# EtherWiz_A4.net
KiCad netlist of a schematic drawn in Altium Designer
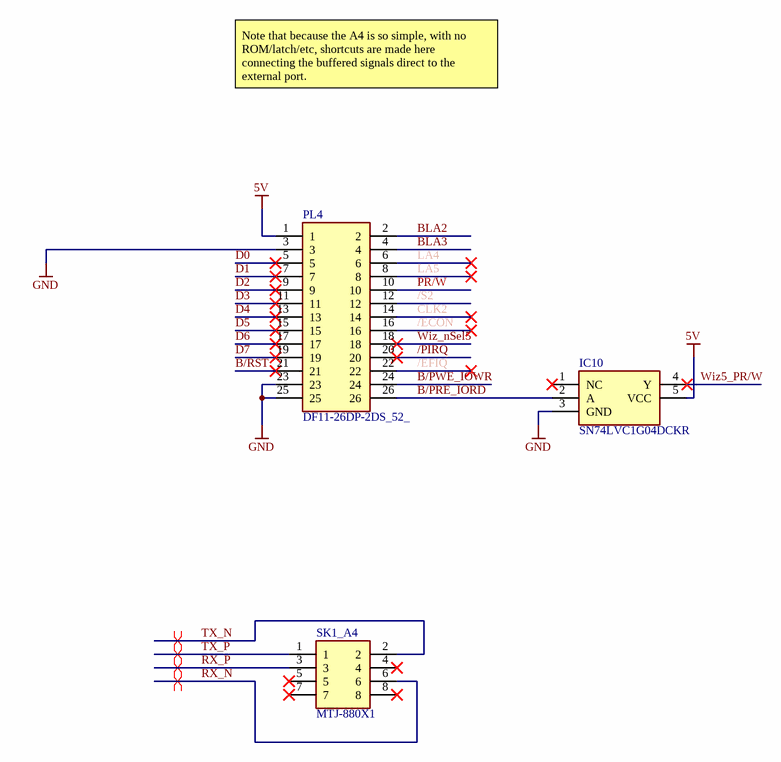
[diagram p0: EtherWiz_A4.SchDoc]

(export (version "E")
  (design (tool "Eeschema 10.0.6"))
  (components
    (comp (ref "IC10")
      (value "SN74LVC1G04DCKR")
      (footprint "SamacSys:SOT65P210X110-5N")
      (description "Integrated Circuit")
      (fields (field (name "MOUSER PART NUMBER") "595-SN74LVC1G04DCKR"))
      (libsource (lib "*") (part "SN74LVC1G04DCKR"))
    )
    (comp (ref "PL4")
      (value "DF11-26DP-2DS_52_")
      (footprint "SamacSys:SHDRRA26W50P200_2X13_2800X1000X500P")
      (description "Connector")
      (fields
        (field (name "MANUFACTURER_PART_NUMBER") "DF11-26DP-2DS(52)")
        (field (name "MOUSER PART NUMBER") "798-DF11-26DP-2DS52")
      )
      (libsource (lib "*") (part "DF11-26DP-2DS_52_"))
    )
    (comp (ref "SK1_A4")
      (value "MTJ-880X1")
      (footprint "SamacSys:MTJ880X1")
      (description "Connector")
      (fields (field (name "MOUSER PART NUMBER") "737-MTJ-880X1"))
      (libsource (lib "*") (part "MTJ-880X1"))
    )
  )
  (nets
    (net (code "1") (name "/BLA2") (class "Default")
      (node (ref "PL4") (pin "2") (pinfunction "2_2") (pintype "passive"))
    )
    (net (code "2") (name "/BLA3") (class "Default")
      (node (ref "PL4") (pin "4") (pinfunction "4_4") (pintype "passive"))
    )
    (net (code "3") (name "/B{slash}PRE_IORD") (class "Default")
      (node (ref "IC10") (pin "2") (pinfunction "A_2") (pintype "passive"))
      (node (ref "PL4") (pin "26") (pinfunction "26_26") (pintype "passive"))
    )
    (net (code "4") (name "/B{slash}PWE_IOWR") (class "Default")
      (node (ref "PL4") (pin "24") (pinfunction "24_24") (pintype "passive"))
    )
    (net (code "5") (name "/B{slash}RST") (class "Default")
      (node (ref "PL4") (pin "21") (pinfunction "21_21") (pintype "passive+no_connect"))
    )
    (net (code "6") (name "/CLK2") (class "Default")
      (node (ref "PL4") (pin "14") (pinfunction "14_14") (pintype "passive+no_connect"))
    )
    (net (code "7") (name "/D0") (class "Default")
      (node (ref "PL4") (pin "5") (pinfunction "5_5") (pintype "passive+no_connect"))
    )
    (net (code "8") (name "/D1") (class "Default")
      (node (ref "PL4") (pin "7") (pinfunction "7_7") (pintype "passive+no_connect"))
    )
    (net (code "9") (name "/D2") (class "Default")
      (node (ref "PL4") (pin "9") (pinfunction "9_9") (pintype "passive+no_connect"))
    )
    (net (code "10") (name "/D3") (class "Default")
      (node (ref "PL4") (pin "11") (pinfunction "11_11") (pintype "passive+no_connect"))
    )
    (net (code "11") (name "/D4") (class "Default")
      (node (ref "PL4") (pin "13") (pinfunction "13_13") (pintype "passive+no_connect"))
    )
    (net (code "12") (name "/D5") (class "Default")
      (node (ref "PL4") (pin "15") (pinfunction "15_15") (pintype "passive+no_connect"))
    )
    (net (code "13") (name "/D6") (class "Default")
      (node (ref "PL4") (pin "17") (pinfunction "17_17") (pintype "passive+no_connect"))
    )
    (net (code "14") (name "/D7") (class "Default")
      (node (ref "PL4") (pin "19") (pinfunction "19_19") (pintype "passive+no_connect"))
    )
    (net (code "15") (name "/LA4") (class "Default")
      (node (ref "PL4") (pin "6") (pinfunction "6_6") (pintype "passive+no_connect"))
    )
    (net (code "16") (name "/LA5") (class "Default")
      (node (ref "PL4") (pin "8") (pinfunction "8_8") (pintype "passive+no_connect"))
    )
    (net (code "17") (name "/PR{slash}W") (class "Default")
      (node (ref "PL4") (pin "10") (pinfunction "10_10") (pintype "passive"))
    )
    (net (code "18") (name "/RX_N") (class "Default")
      (node (ref "SK1_A4") (pin "6") (pinfunction "6_6") (pintype "passive"))
    )
    (net (code "19") (name "/RX_P") (class "Default")
      (node (ref "SK1_A4") (pin "3") (pinfunction "3_3") (pintype "passive"))
    )
    (net (code "20") (name "/TX_N") (class "Default")
      (node (ref "SK1_A4") (pin "2") (pinfunction "2_2") (pintype "passive"))
    )
    (net (code "21") (name "/TX_P") (class "Default")
      (node (ref "SK1_A4") (pin "1") (pinfunction "1_1") (pintype "passive"))
    )
    (net (code "22") (name "/Wiz5_PR{slash}W") (class "Default")
      (node (ref "IC10") (pin "4") (pinfunction "Y_4") (pintype "passive+no_connect"))
    )
    (net (code "23") (name "/Wiz_nSel5") (class "Default")
      (node (ref "PL4") (pin "18") (pinfunction "18_18") (pintype "passive+no_connect"))
    )
    (net (code "24") (name "/{slash}ECON") (class "Default")
      (node (ref "PL4") (pin "16") (pinfunction "16_16") (pintype "passive+no_connect"))
    )
    (net (code "25") (name "/{slash}EFIQ") (class "Default")
      (node (ref "PL4") (pin "22") (pinfunction "22_22") (pintype "passive+no_connect"))
    )
    (net (code "26") (name "/{slash}PIRQ") (class "Default")
      (node (ref "PL4") (pin "20") (pinfunction "20_20") (pintype "passive+no_connect"))
    )
    (net (code "27") (name "/{slash}S2") (class "Default")
      (node (ref "PL4") (pin "12") (pinfunction "12_12") (pintype "passive"))
    )
    (net (code "28") (name "5V") (class "Default")
      (node (ref "IC10") (pin "5") (pinfunction "VCC_5") (pintype "passive"))
      (node (ref "PL4") (pin "1") (pinfunction "1_1") (pintype "passive"))
    )
    (net (code "29") (name "GND") (class "Default")
      (node (ref "IC10") (pin "3") (pinfunction "GND_3") (pintype "passive"))
      (node (ref "PL4") (pin "23") (pinfunction "23_23") (pintype "passive"))
      (node (ref "PL4") (pin "25") (pinfunction "25_25") (pintype "passive"))
      (node (ref "PL4") (pin "3") (pinfunction "3_3") (pintype "passive"))
    )
    (net (code "30") (name "unconnected-(IC10-NC-Pad1)") (class "Default")
      (node (ref "IC10") (pin "1") (pinfunction "NC_1") (pintype "passive+no_connect"))
    )
    (net (code "31") (name "unconnected-(SK1_A4-Pad4)") (class "Default")
      (node (ref "SK1_A4") (pin "4") (pinfunction "4_4") (pintype "passive+no_connect"))
    )
    (net (code "32") (name "unconnected-(SK1_A4-Pad5)") (class "Default")
      (node (ref "SK1_A4") (pin "5") (pinfunction "5_5") (pintype "passive+no_connect"))
    )
    (net (code "33") (name "unconnected-(SK1_A4-Pad7)") (class "Default")
      (node (ref "SK1_A4") (pin "7") (pinfunction "7_7") (pintype "passive+no_connect"))
    )
    (net (code "34") (name "unconnected-(SK1_A4-Pad8)") (class "Default")
      (node (ref "SK1_A4") (pin "8") (pinfunction "8_8") (pintype "passive+no_connect"))
    )
  )
)
